# TopLevelDesign.net
KiCad netlist of a schematic drawn in Altium Designer
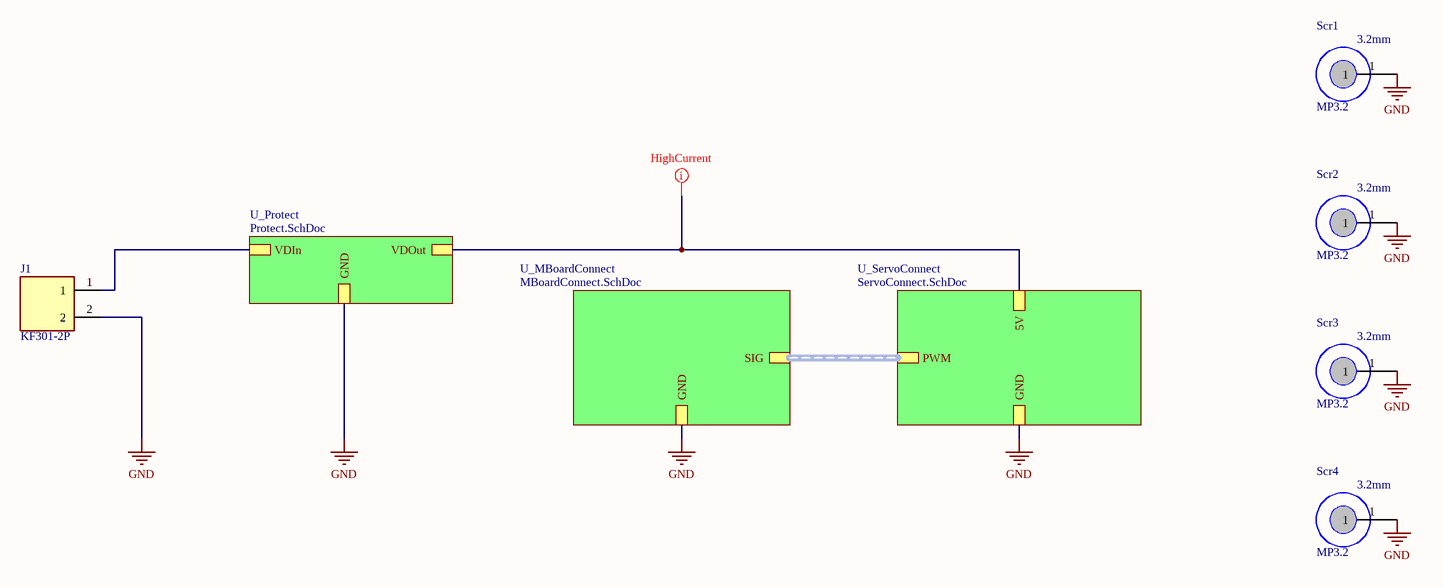
[diagram p0: TopLevelDesign.SchDoc]

(export (version "E")
  (design (tool "Eeschema 10.0.6"))
  (components
    (comp (ref "J1")
      (value "KF301-2P")
      (footprint "HANDSON_KF301-2P")
      (description "2 Pin Terminal Block 5mm Pitch")
      (libsource (lib "Tin Tran") (part "KF301-2P"))
    )
    (comp (ref "Scr1") (value "MP3.2") (footprint "MP3.2") (libsource (lib "Tin Tran") (part "MP3.2")))
    (comp (ref "Scr2") (value "MP3.2") (footprint "MP3.2") (libsource (lib "Tin Tran") (part "MP3.2")))
    (comp (ref "Scr3") (value "MP3.2") (footprint "MP3.2") (libsource (lib "Tin Tran") (part "MP3.2")))
    (comp (ref "Scr4") (value "MP3.2") (footprint "MP3.2") (libsource (lib "Tin Tran") (part "MP3.2")))
  )
  (nets
    (net (code "3") (name "/VDIn") (class "Default")
      (node (ref "J1") (pin "1") (pinfunction "1_1") (pintype "passive"))
    )
    (net (code "4") (name "GND") (class "Default")
      (node (ref "J1") (pin "2") (pinfunction "2_2") (pintype "passive"))
      (node (ref "Scr1") (pin "1") (pinfunction "1_1") (pintype "passive"))
      (node (ref "Scr2") (pin "1") (pinfunction "1_1") (pintype "passive"))
      (node (ref "Scr3") (pin "1") (pinfunction "1_1") (pintype "passive"))
      (node (ref "Scr4") (pin "1") (pinfunction "1_1") (pintype "passive"))
    )
  )
)
